# PSoC_PyunPyun_Mini.net
KiCad netlist of a schematic drawn in EAGLE
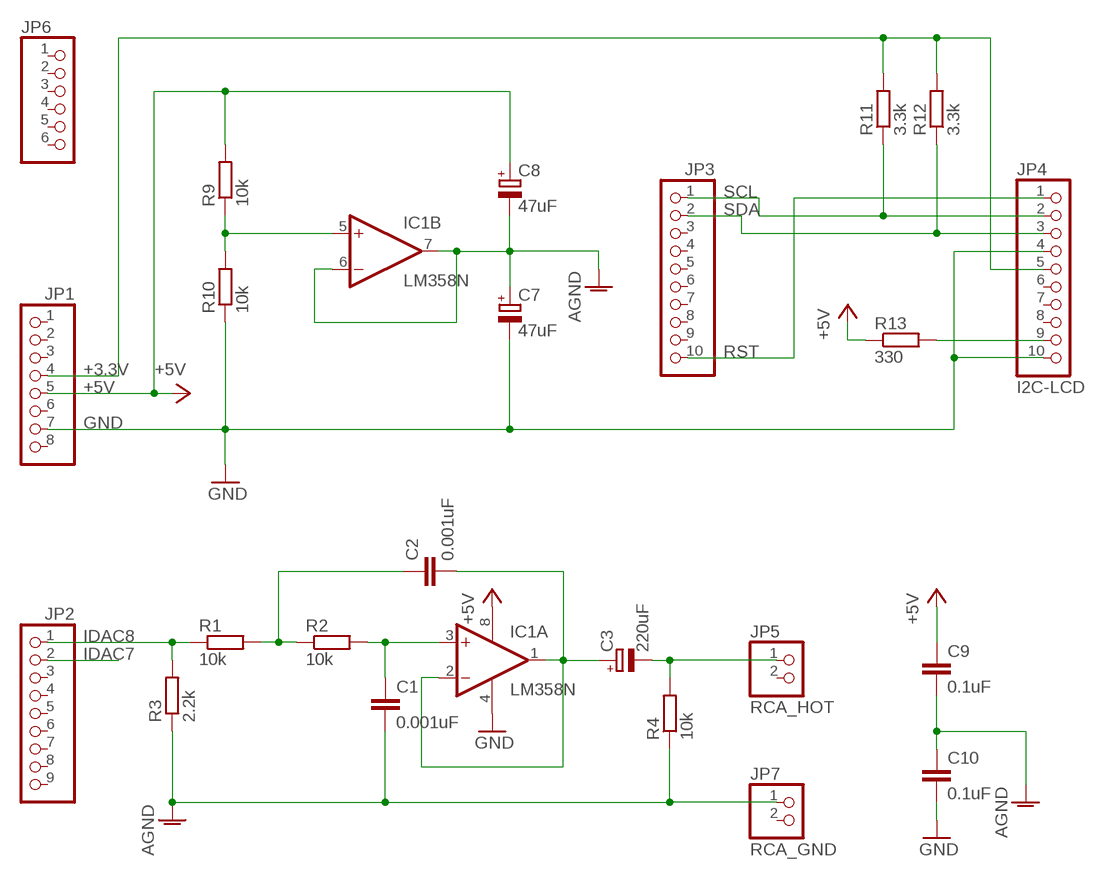
[diagram p0: schematic, sheet 1]

(export (version "E")
  (design (tool "Eeschema 10.0.6"))
  (components
    (comp (ref "C1")
      (value "0.001uF")
      (footprint "eagle-import:C050-024X044")
      (libsource (lib "eagle-import") (part "C-EU050-024X044"))
    )
    (comp (ref "C2")
      (value "0.001uF")
      (footprint "eagle-import:C050-024X044")
      (libsource (lib "eagle-import") (part "C-EU050-024X044"))
    )
    (comp (ref "C3")
      (value "220uF")
      (footprint "eagle-import:E5-8,5")
      (libsource (lib "eagle-import") (part "CPOL-EUE5-8.5"))
    )
    (comp (ref "C7")
      (value "47uF")
      (footprint "eagle-import:E5-5")
      (libsource (lib "eagle-import") (part "CPOL-EUE5-5"))
    )
    (comp (ref "C8")
      (value "47uF")
      (footprint "eagle-import:E5-5")
      (libsource (lib "eagle-import") (part "CPOL-EUE5-5"))
    )
    (comp (ref "C9")
      (value "0.1uF")
      (footprint "eagle-import:C050-024X044")
      (libsource (lib "eagle-import") (part "C-EU050-024X044"))
    )
    (comp (ref "C10")
      (value "0.1uF")
      (footprint "eagle-import:C050-024X044")
      (libsource (lib "eagle-import") (part "C-EU050-024X044"))
    )
    (comp (ref "IC1")
      (value "LM358N")
      (footprint "eagle-import:DIL08")
      (libsource (lib "eagle-import") (part "LM358N"))
    )
    (comp (ref "JP1")
      (value "PINHD-1X8")
      (footprint "eagle-import:1X08")
      (libsource (lib "eagle-import") (part "PINHD-1X8"))
    )
    (comp (ref "JP2")
      (value "PINHD-1X9")
      (footprint "eagle-import:1X09")
      (libsource (lib "eagle-import") (part "PINHD-1X9"))
    )
    (comp (ref "JP3")
      (value "PINHD-1X10")
      (footprint "eagle-import:1X10")
      (libsource (lib "eagle-import") (part "PINHD-1X10"))
    )
    (comp (ref "JP4")
      (value "I2C-LCD")
      (footprint "eagle-import:1X10")
      (libsource (lib "eagle-import") (part "PINHD-1X10"))
    )
    (comp (ref "JP5")
      (value "RCA_HOT")
      (footprint "eagle-import:1X02")
      (libsource (lib "eagle-import") (part "PINHD-1X2"))
    )
    (comp (ref "JP6")
      (value "PINHD-1X6")
      (footprint "eagle-import:1X06")
      (libsource (lib "eagle-import") (part "PINHD-1X6"))
    )
    (comp (ref "JP7")
      (value "RCA_GND")
      (footprint "eagle-import:1X02")
      (libsource (lib "eagle-import") (part "PINHD-1X2"))
    )
    (comp (ref "R1")
      (value "10k")
      (footprint "eagle-import:0207_7")
      (libsource (lib "eagle-import") (part "R-EU_0207/7"))
    )
    (comp (ref "R2")
      (value "10k")
      (footprint "eagle-import:0207_7")
      (libsource (lib "eagle-import") (part "R-EU_0207/7"))
    )
    (comp (ref "R3")
      (value "2.2k")
      (footprint "eagle-import:0207_7")
      (libsource (lib "eagle-import") (part "R-EU_0207/7"))
    )
    (comp (ref "R4")
      (value "10k")
      (footprint "eagle-import:0207_7")
      (libsource (lib "eagle-import") (part "R-EU_0207/7"))
    )
    (comp (ref "R9")
      (value "10k")
      (footprint "eagle-import:0207_7")
      (libsource (lib "eagle-import") (part "R-EU_0207/7"))
    )
    (comp (ref "R10")
      (value "10k")
      (footprint "eagle-import:0207_7")
      (libsource (lib "eagle-import") (part "R-EU_0207/7"))
    )
    (comp (ref "R11")
      (value "3.3k")
      (footprint "eagle-import:0207_7")
      (libsource (lib "eagle-import") (part "R-EU_0207/7"))
    )
    (comp (ref "R12")
      (value "3.3k")
      (footprint "eagle-import:0207_7")
      (libsource (lib "eagle-import") (part "R-EU_0207/7"))
    )
    (comp (ref "R13")
      (value "330")
      (footprint "eagle-import:0207_7")
      (libsource (lib "eagle-import") (part "R-EU_0207/7"))
    )
  )
  (nets
    (net (code "1") (name "+5V") (class "Default")
      (node (ref "C8") (pin "+") (pinfunction "+_+") (pintype "passive"))
      (node (ref "C9") (pin "1") (pinfunction "1_1") (pintype "passive"))
      (node (ref "IC1") (pin "8") (pinfunction "V+_8") (pintype "power_in"))
      (node (ref "JP1") (pin "5") (pinfunction "5_5") (pintype "passive"))
      (node (ref "R13") (pin "1") (pinfunction "1_1") (pintype "passive"))
      (node (ref "R9") (pin "2") (pinfunction "2_2") (pintype "passive"))
    )
    (net (code "2") (name "/+3.3V") (class "Default")
      (node (ref "JP1") (pin "4") (pinfunction "4_4") (pintype "passive"))
      (node (ref "JP4") (pin "5") (pinfunction "5_5") (pintype "passive"))
      (node (ref "R11") (pin "2") (pinfunction "2_2") (pintype "passive"))
      (node (ref "R12") (pin "2") (pinfunction "2_2") (pintype "passive"))
    )
    (net (code "3") (name "/IDAC7") (class "Default")
      (node (ref "JP2") (pin "2") (pinfunction "2_2") (pintype "passive"))
    )
    (net (code "4") (name "/IDAC8") (class "Default")
      (node (ref "JP2") (pin "1") (pinfunction "1_1") (pintype "passive"))
      (node (ref "R1") (pin "1") (pinfunction "1_1") (pintype "passive"))
      (node (ref "R3") (pin "2") (pinfunction "2_2") (pintype "passive"))
    )
    (net (code "5") (name "/RST") (class "Default")
      (node (ref "JP3") (pin "10") (pinfunction "10_10") (pintype "passive"))
      (node (ref "JP4") (pin "1") (pinfunction "1_1") (pintype "passive"))
    )
    (net (code "6") (name "/SCL") (class "Default")
      (node (ref "JP3") (pin "1") (pinfunction "1_1") (pintype "passive"))
      (node (ref "JP4") (pin "2") (pinfunction "2_2") (pintype "passive"))
      (node (ref "R11") (pin "1") (pinfunction "1_1") (pintype "passive"))
    )
    (net (code "7") (name "/SDA") (class "Default")
      (node (ref "JP3") (pin "2") (pinfunction "2_2") (pintype "passive"))
      (node (ref "JP4") (pin "3") (pinfunction "3_3") (pintype "passive"))
      (node (ref "R12") (pin "1") (pinfunction "1_1") (pintype "passive"))
    )
    (net (code "8") (name "AGND") (class "Default")
      (node (ref "C1") (pin "2") (pinfunction "2_2") (pintype "passive"))
      (node (ref "C10") (pin "1") (pinfunction "1_1") (pintype "passive"))
      (node (ref "C7") (pin "+") (pinfunction "+_+") (pintype "passive"))
      (node (ref "C8") (pin "-") (pinfunction "-_-") (pintype "passive"))
      (node (ref "C9") (pin "2") (pinfunction "2_2") (pintype "passive"))
      (node (ref "IC1") (pin "6") (pinfunction "-IN_6") (pintype "input"))
      (node (ref "IC1") (pin "7") (pinfunction "OUT_7") (pintype "output"))
      (node (ref "JP7") (pin "1") (pinfunction "1_1") (pintype "passive"))
      (node (ref "R3") (pin "1") (pinfunction "1_1") (pintype "passive"))
      (node (ref "R4") (pin "1") (pinfunction "1_1") (pintype "passive"))
    )
    (net (code "9") (name "GND") (class "Default")
      (node (ref "C10") (pin "2") (pinfunction "2_2") (pintype "passive"))
      (node (ref "C7") (pin "-") (pinfunction "-_-") (pintype "passive"))
      (node (ref "IC1") (pin "4") (pinfunction "V-_4") (pintype "power_in"))
      (node (ref "JP1") (pin "7") (pinfunction "7_7") (pintype "passive"))
      (node (ref "JP4") (pin "10") (pinfunction "10_10") (pintype "passive"))
      (node (ref "JP4") (pin "4") (pinfunction "4_4") (pintype "passive"))
      (node (ref "R10") (pin "1") (pinfunction "1_1") (pintype "passive"))
    )
    (net (code "10") (name "Net-(C2-Pad1)") (class "Default")
      (node (ref "C2") (pin "1") (pinfunction "1_1") (pintype "passive"))
      (node (ref "R1") (pin "2") (pinfunction "2_2") (pintype "passive"))
      (node (ref "R2") (pin "1") (pinfunction "1_1") (pintype "passive"))
    )
    (net (code "11") (name "Net-(C3-Pad-)") (class "Default")
      (node (ref "C3") (pin "-") (pinfunction "-_-") (pintype "passive"))
      (node (ref "JP5") (pin "1") (pinfunction "1_1") (pintype "passive"))
      (node (ref "R4") (pin "2") (pinfunction "2_2") (pintype "passive"))
    )
    (net (code "12") (name "Net-(IC1A-+IN)") (class "Default")
      (node (ref "C1") (pin "1") (pinfunction "1_1") (pintype "passive"))
      (node (ref "IC1") (pin "3") (pinfunction "+IN_3") (pintype "input"))
      (node (ref "R2") (pin "2") (pinfunction "2_2") (pintype "passive"))
    )
    (net (code "13") (name "Net-(IC1A--IN)") (class "Default")
      (node (ref "C2") (pin "2") (pinfunction "2_2") (pintype "passive"))
      (node (ref "C3") (pin "+") (pinfunction "+_+") (pintype "passive"))
      (node (ref "IC1") (pin "1") (pinfunction "OUT_1") (pintype "output"))
      (node (ref "IC1") (pin "2") (pinfunction "-IN_2") (pintype "input"))
    )
    (net (code "14") (name "Net-(IC1B-+IN)") (class "Default")
      (node (ref "IC1") (pin "5") (pinfunction "+IN_5") (pintype "input"))
      (node (ref "R10") (pin "2") (pinfunction "2_2") (pintype "passive"))
      (node (ref "R9") (pin "1") (pinfunction "1_1") (pintype "passive"))
    )
    (net (code "15") (name "Net-(JP4-Pad9)") (class "Default")
      (node (ref "JP4") (pin "9") (pinfunction "9_9") (pintype "passive"))
      (node (ref "R13") (pin "2") (pinfunction "2_2") (pintype "passive"))
    )
    (net (code "16") (name "unconnected-(JP1-Pad1)") (class "Default")
      (node (ref "JP1") (pin "1") (pinfunction "1_1") (pintype "passive"))
    )
    (net (code "17") (name "unconnected-(JP1-Pad2)") (class "Default")
      (node (ref "JP1") (pin "2") (pinfunction "2_2") (pintype "passive"))
    )
    (net (code "18") (name "unconnected-(JP1-Pad3)") (class "Default")
      (node (ref "JP1") (pin "3") (pinfunction "3_3") (pintype "passive"))
    )
    (net (code "19") (name "unconnected-(JP1-Pad6)") (class "Default")
      (node (ref "JP1") (pin "6") (pinfunction "6_6") (pintype "passive"))
    )
    (net (code "20") (name "unconnected-(JP1-Pad8)") (class "Default")
      (node (ref "JP1") (pin "8") (pinfunction "8_8") (pintype "passive"))
    )
    (net (code "21") (name "unconnected-(JP2-Pad3)") (class "Default")
      (node (ref "JP2") (pin "3") (pinfunction "3_3") (pintype "passive"))
    )
    (net (code "22") (name "unconnected-(JP2-Pad4)") (class "Default")
      (node (ref "JP2") (pin "4") (pinfunction "4_4") (pintype "passive"))
    )
    (net (code "23") (name "unconnected-(JP2-Pad5)") (class "Default")
      (node (ref "JP2") (pin "5") (pinfunction "5_5") (pintype "passive"))
    )
    (net (code "24") (name "unconnected-(JP2-Pad6)") (class "Default")
      (node (ref "JP2") (pin "6") (pinfunction "6_6") (pintype "passive"))
    )
    (net (code "25") (name "unconnected-(JP2-Pad7)") (class "Default")
      (node (ref "JP2") (pin "7") (pinfunction "7_7") (pintype "passive"))
    )
    (net (code "26") (name "unconnected-(JP2-Pad8)") (class "Default")
      (node (ref "JP2") (pin "8") (pinfunction "8_8") (pintype "passive"))
    )
    (net (code "27") (name "unconnected-(JP2-Pad9)") (class "Default")
      (node (ref "JP2") (pin "9") (pinfunction "9_9") (pintype "passive"))
    )
    (net (code "28") (name "unconnected-(JP3-Pad3)") (class "Default")
      (node (ref "JP3") (pin "3") (pinfunction "3_3") (pintype "passive"))
    )
    (net (code "29") (name "unconnected-(JP3-Pad4)") (class "Default")
      (node (ref "JP3") (pin "4") (pinfunction "4_4") (pintype "passive"))
    )
    (net (code "30") (name "unconnected-(JP3-Pad5)") (class "Default")
      (node (ref "JP3") (pin "5") (pinfunction "5_5") (pintype "passive"))
    )
    (net (code "31") (name "unconnected-(JP3-Pad6)") (class "Default")
      (node (ref "JP3") (pin "6") (pinfunction "6_6") (pintype "passive"))
    )
    (net (code "32") (name "unconnected-(JP3-Pad7)") (class "Default")
      (node (ref "JP3") (pin "7") (pinfunction "7_7") (pintype "passive"))
    )
    (net (code "33") (name "unconnected-(JP3-Pad8)") (class "Default")
      (node (ref "JP3") (pin "8") (pinfunction "8_8") (pintype "passive"))
    )
    (net (code "34") (name "unconnected-(JP3-Pad9)") (class "Default")
      (node (ref "JP3") (pin "9") (pinfunction "9_9") (pintype "passive"))
    )
    (net (code "35") (name "unconnected-(JP4-Pad6)") (class "Default")
      (node (ref "JP4") (pin "6") (pinfunction "6_6") (pintype "passive"))
    )
    (net (code "36") (name "unconnected-(JP4-Pad7)") (class "Default")
      (node (ref "JP4") (pin "7") (pinfunction "7_7") (pintype "passive"))
    )
    (net (code "37") (name "unconnected-(JP4-Pad8)") (class "Default")
      (node (ref "JP4") (pin "8") (pinfunction "8_8") (pintype "passive"))
    )
    (net (code "38") (name "unconnected-(JP5-Pad2)") (class "Default")
      (node (ref "JP5") (pin "2") (pinfunction "2_2") (pintype "passive"))
    )
    (net (code "39") (name "unconnected-(JP6-Pad1)") (class "Default")
      (node (ref "JP6") (pin "1") (pinfunction "1_1") (pintype "passive"))
    )
    (net (code "40") (name "unconnected-(JP6-Pad2)") (class "Default")
      (node (ref "JP6") (pin "2") (pinfunction "2_2") (pintype "passive"))
    )
    (net (code "41") (name "unconnected-(JP6-Pad3)") (class "Default")
      (node (ref "JP6") (pin "3") (pinfunction "3_3") (pintype "passive"))
    )
    (net (code "42") (name "unconnected-(JP6-Pad4)") (class "Default")
      (node (ref "JP6") (pin "4") (pinfunction "4_4") (pintype "passive"))
    )
    (net (code "43") (name "unconnected-(JP6-Pad5)") (class "Default")
      (node (ref "JP6") (pin "5") (pinfunction "5_5") (pintype "passive"))
    )
    (net (code "44") (name "unconnected-(JP6-Pad6)") (class "Default")
      (node (ref "JP6") (pin "6") (pinfunction "6_6") (pintype "passive"))
    )
    (net (code "45") (name "unconnected-(JP7-Pad2)") (class "Default")
      (node (ref "JP7") (pin "2") (pinfunction "2_2") (pintype "passive"))
    )
  )
)
